# ram.net
KiCad netlist of a schematic drawn in EAGLE
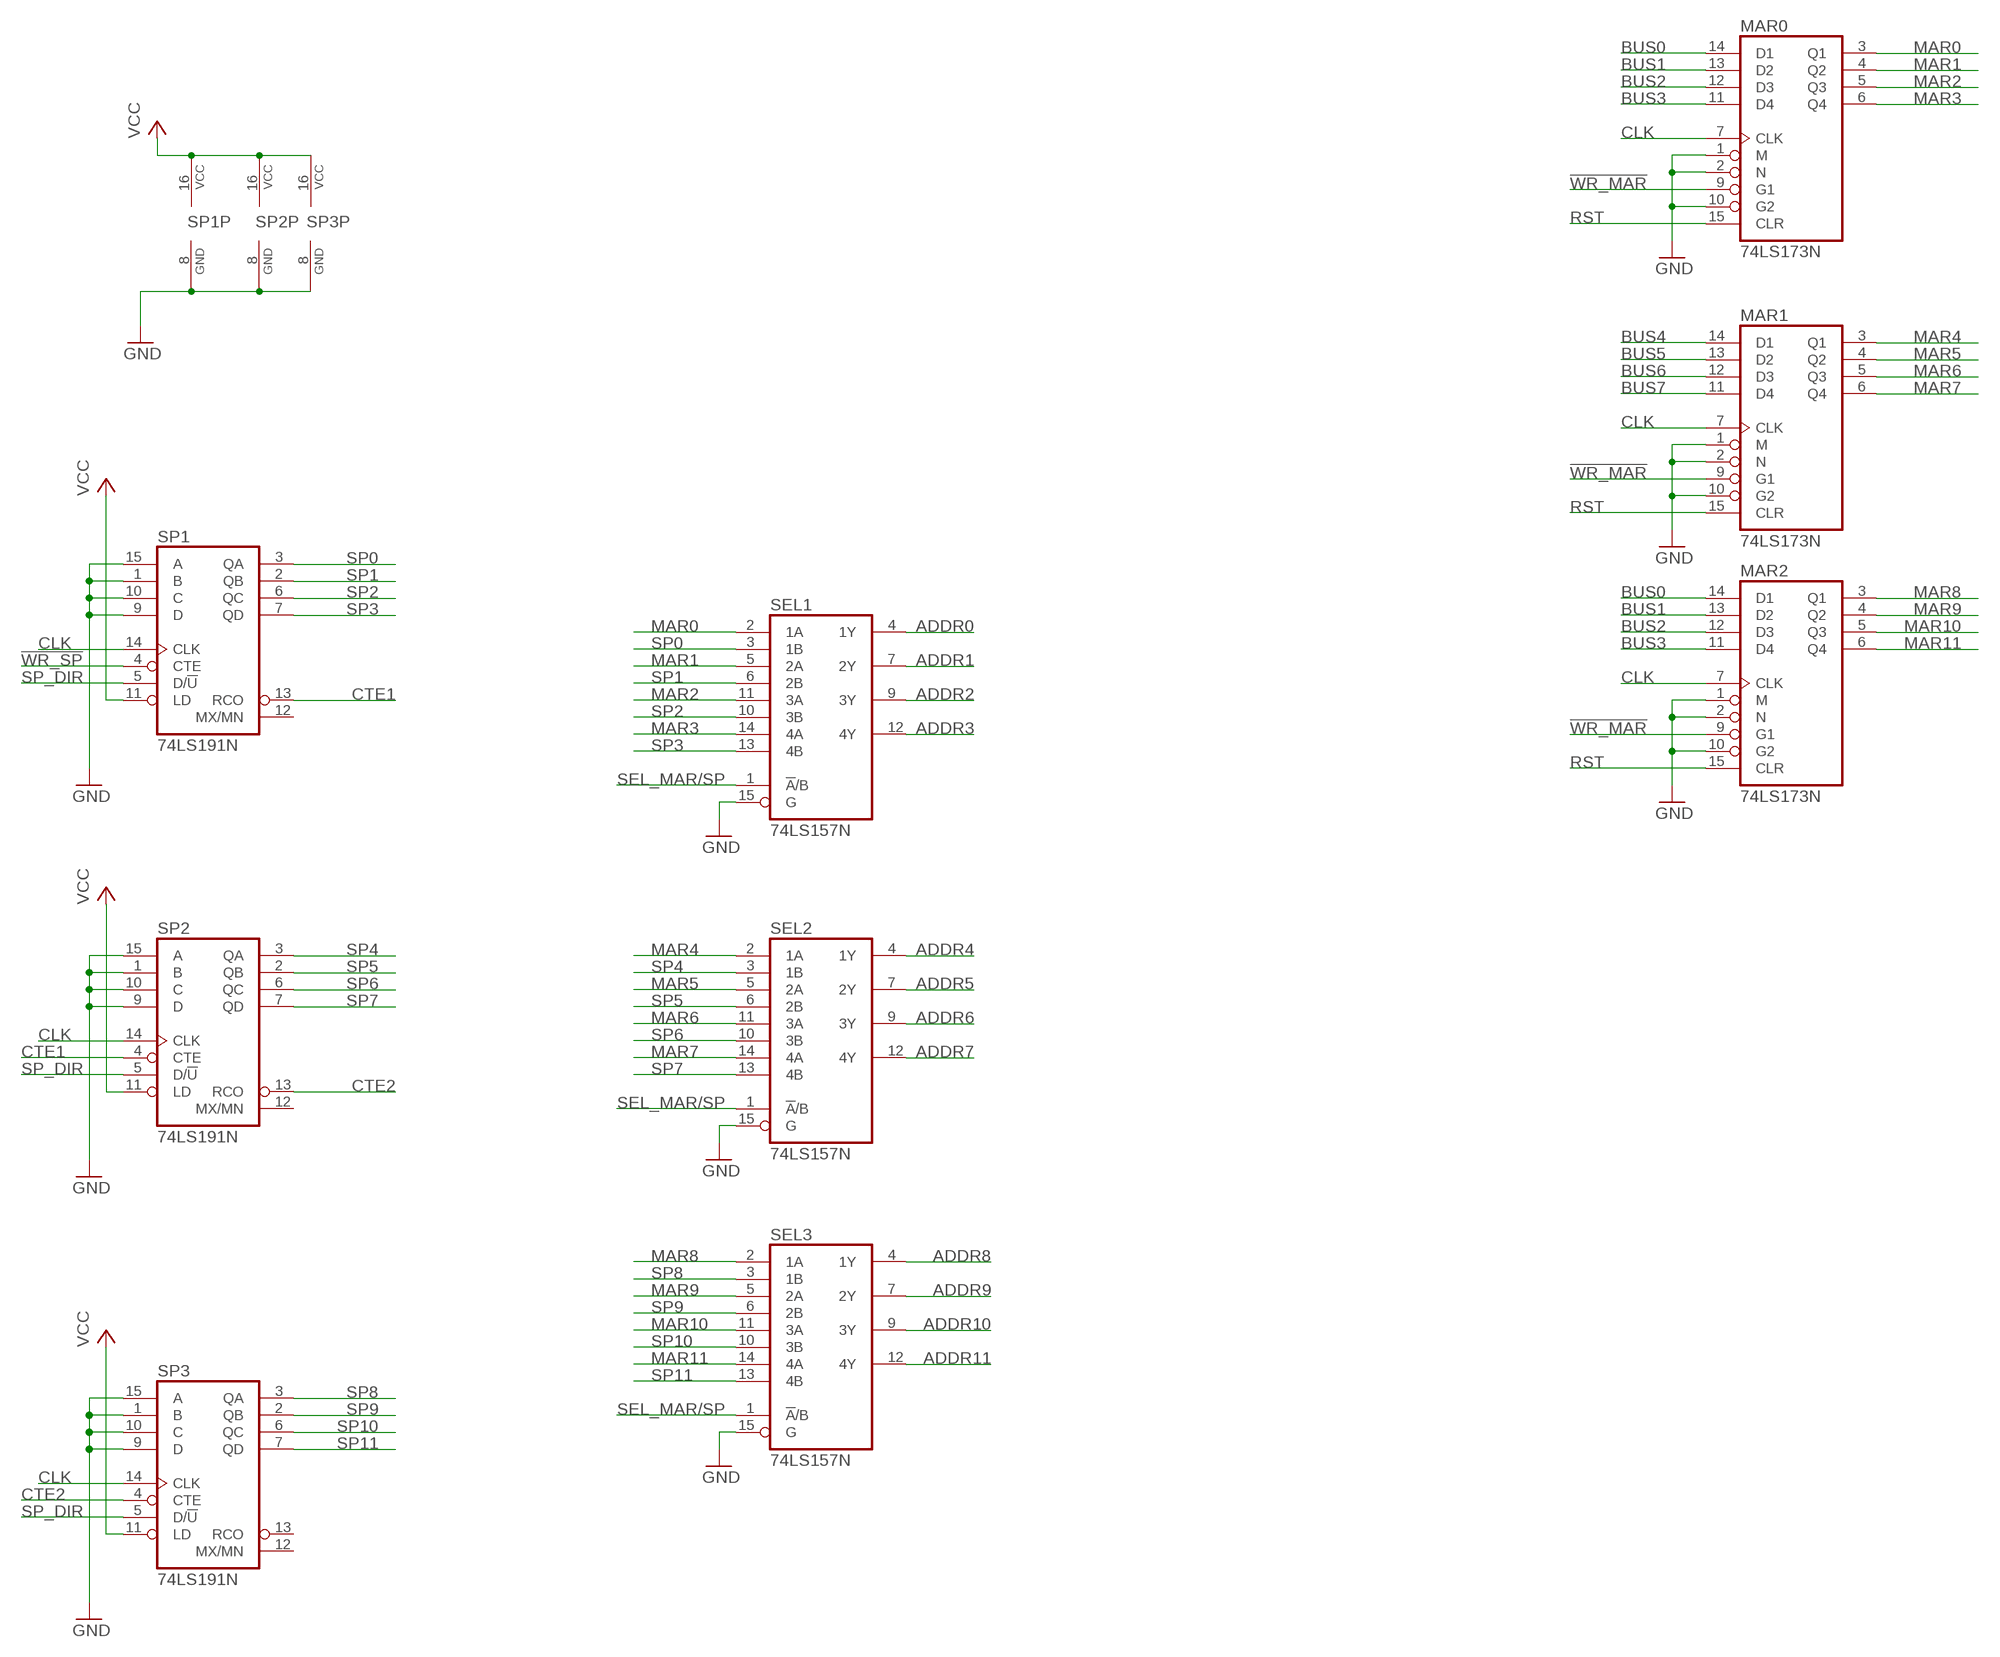
[diagram p0: schematic, sheet 1, part 1 of 2]
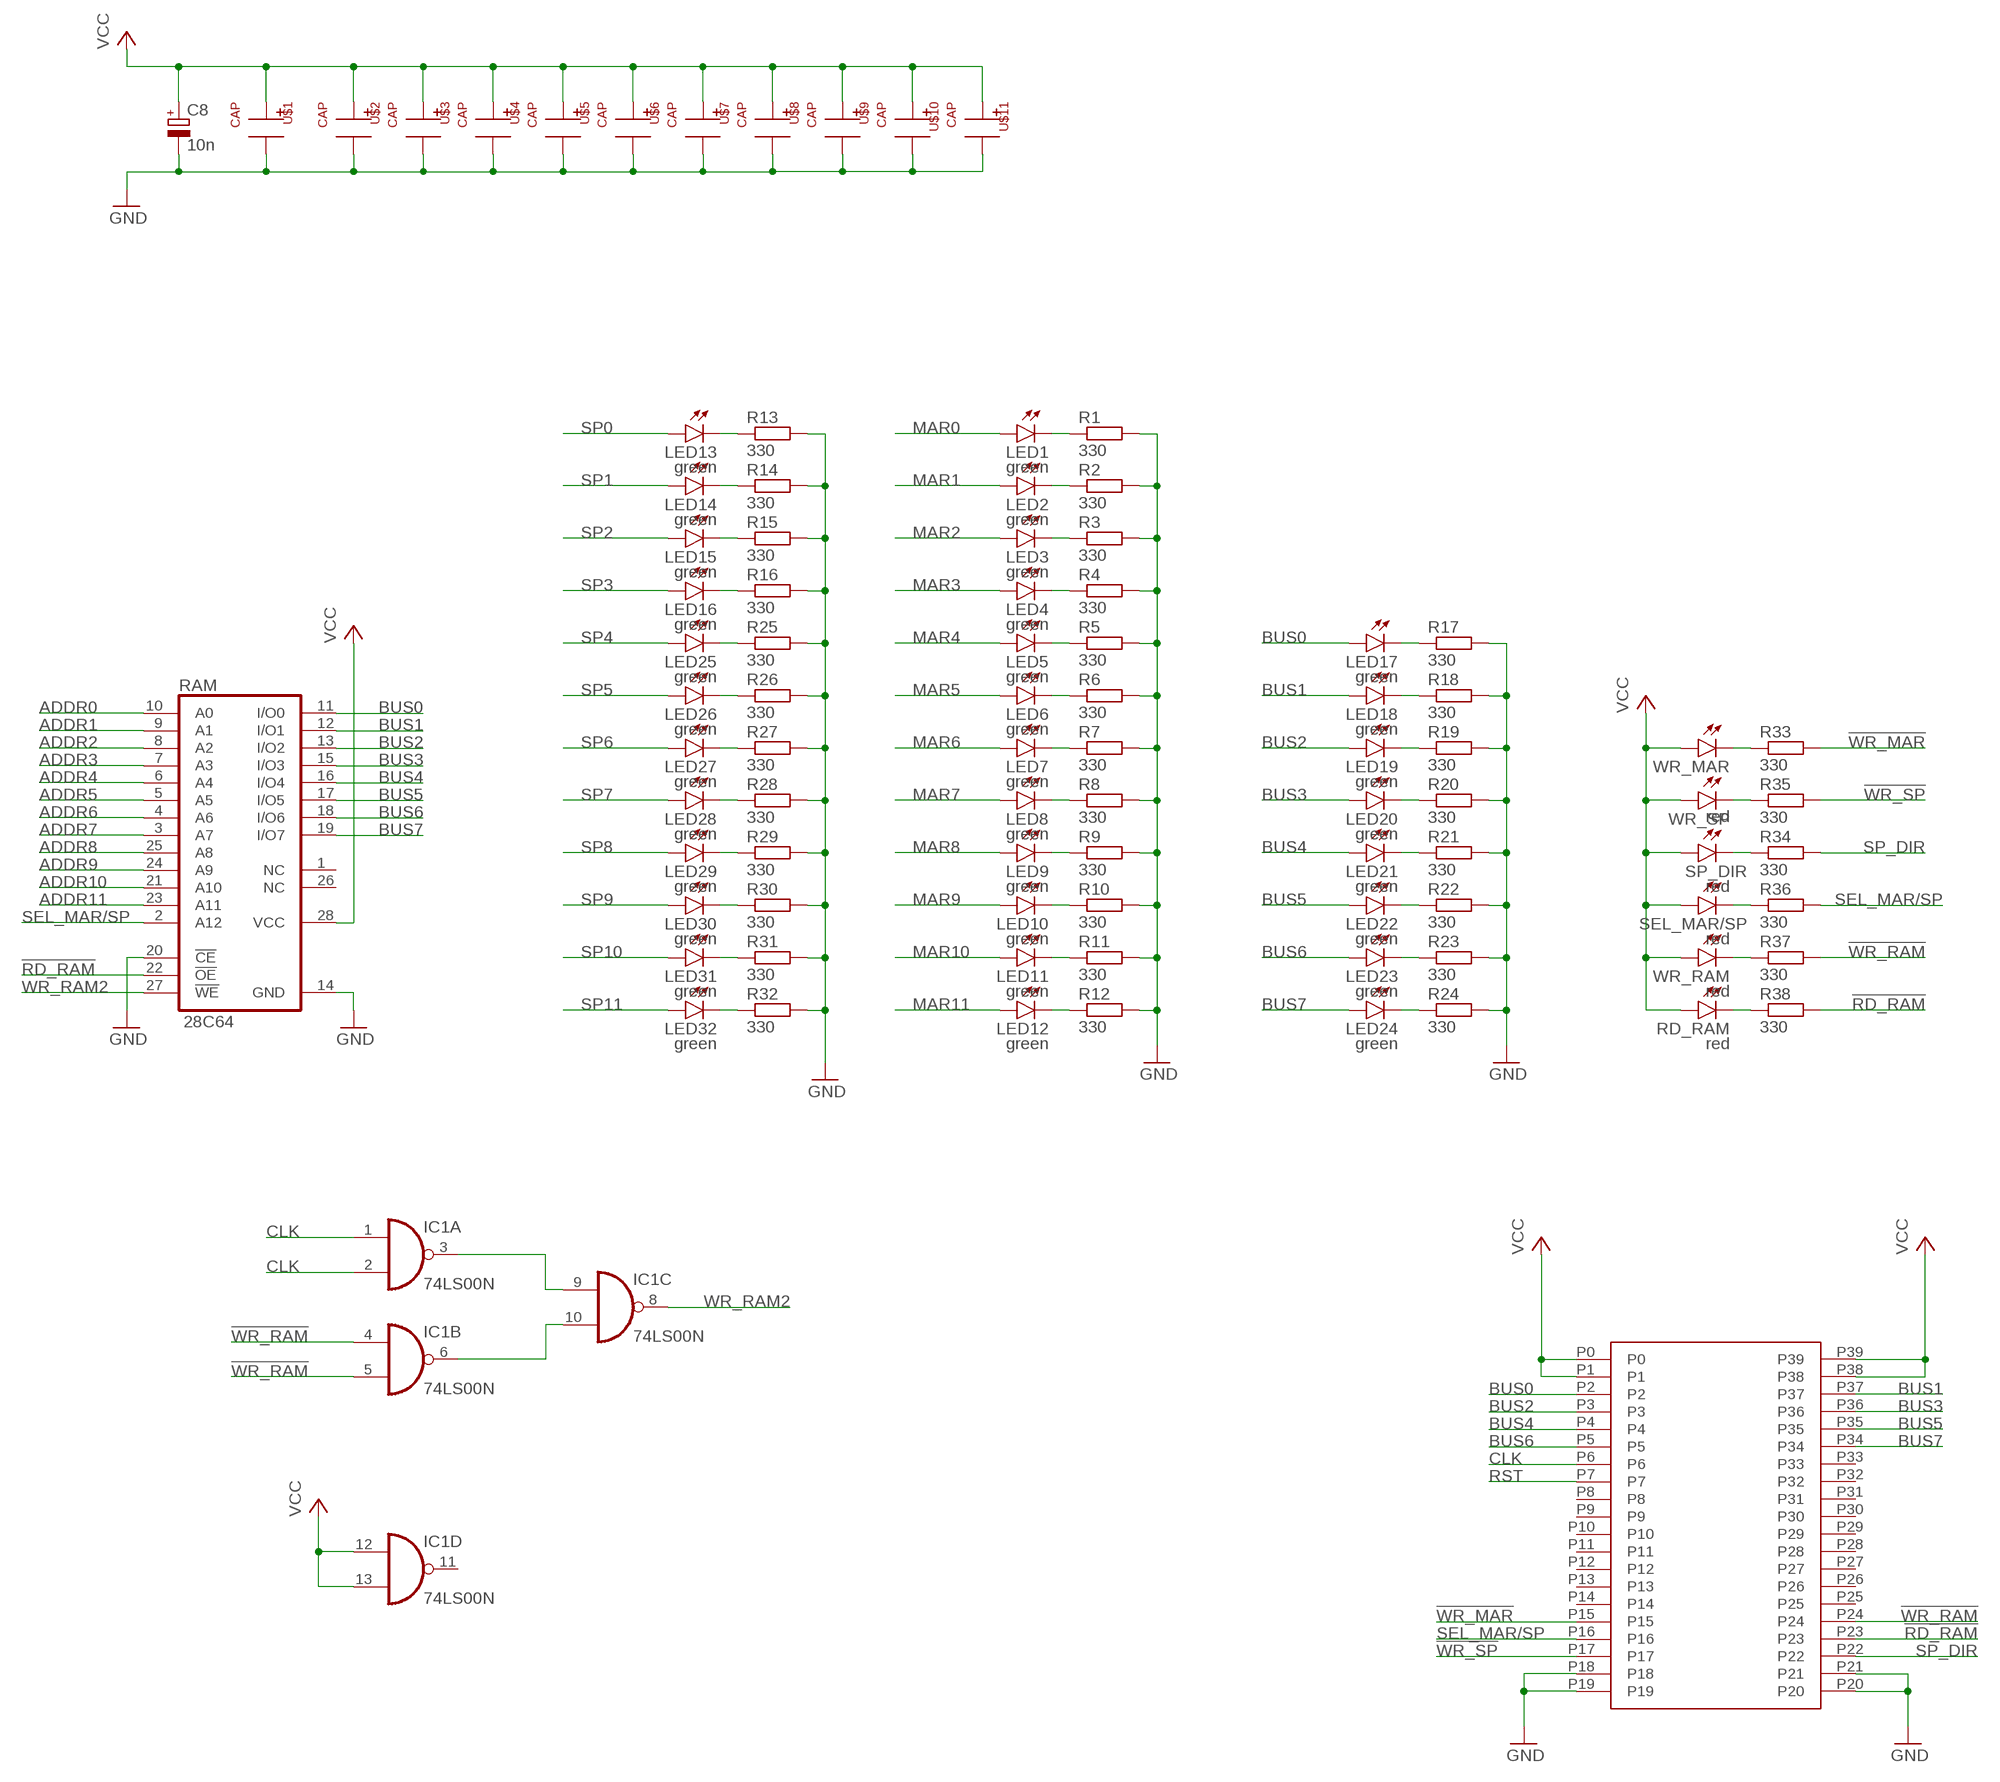
[diagram p1: schematic, sheet 1, part 2 of 2]

(export (version "E")
  (design (tool "Eeschema 10.0.6"))
  (components
    (comp (ref "C8")
      (value "10n")
      (footprint "eagle-import:E2,5-6E")
      (libsource (lib "eagle-import") (part "CPOL-EUE2,5-6E"))
    )
    (comp (ref "IC1")
      (value "74LS00N")
      (footprint "eagle-import:DIL14")
      (libsource (lib "eagle-import") (part "7400NLS"))
    )
    (comp (ref "LED1")
      (value "green")
      (footprint "eagle-import:SML1206")
      (libsource (lib "eagle-import") (part "LEDSML1206"))
    )
    (comp (ref "LED2")
      (value "green")
      (footprint "eagle-import:SML1206")
      (libsource (lib "eagle-import") (part "LEDSML1206"))
    )
    (comp (ref "LED3")
      (value "green")
      (footprint "eagle-import:SML1206")
      (libsource (lib "eagle-import") (part "LEDSML1206"))
    )
    (comp (ref "LED4")
      (value "green")
      (footprint "eagle-import:SML1206")
      (libsource (lib "eagle-import") (part "LEDSML1206"))
    )
    (comp (ref "LED5")
      (value "green")
      (footprint "eagle-import:SML1206")
      (libsource (lib "eagle-import") (part "LEDSML1206"))
    )
    (comp (ref "LED6")
      (value "green")
      (footprint "eagle-import:SML1206")
      (libsource (lib "eagle-import") (part "LEDSML1206"))
    )
    (comp (ref "LED7")
      (value "green")
      (footprint "eagle-import:SML1206")
      (libsource (lib "eagle-import") (part "LEDSML1206"))
    )
    (comp (ref "LED8")
      (value "green")
      (footprint "eagle-import:SML1206")
      (libsource (lib "eagle-import") (part "LEDSML1206"))
    )
    (comp (ref "LED9")
      (value "green")
      (footprint "eagle-import:SML1206")
      (libsource (lib "eagle-import") (part "LEDSML1206"))
    )
    (comp (ref "LED10")
      (value "green")
      (footprint "eagle-import:SML1206")
      (libsource (lib "eagle-import") (part "LEDSML1206"))
    )
    (comp (ref "LED11")
      (value "green")
      (footprint "eagle-import:SML1206")
      (libsource (lib "eagle-import") (part "LEDSML1206"))
    )
    (comp (ref "LED12")
      (value "green")
      (footprint "eagle-import:SML1206")
      (libsource (lib "eagle-import") (part "LEDSML1206"))
    )
    (comp (ref "LED13")
      (value "green")
      (footprint "eagle-import:SML1206")
      (libsource (lib "eagle-import") (part "LEDSML1206"))
    )
    (comp (ref "LED14")
      (value "green")
      (footprint "eagle-import:SML1206")
      (libsource (lib "eagle-import") (part "LEDSML1206"))
    )
    (comp (ref "LED15")
      (value "green")
      (footprint "eagle-import:SML1206")
      (libsource (lib "eagle-import") (part "LEDSML1206"))
    )
    (comp (ref "LED16")
      (value "green")
      (footprint "eagle-import:SML1206")
      (libsource (lib "eagle-import") (part "LEDSML1206"))
    )
    (comp (ref "LED17")
      (value "green")
      (footprint "eagle-import:SML1206")
      (libsource (lib "eagle-import") (part "LEDSML1206"))
    )
    (comp (ref "LED18")
      (value "green")
      (footprint "eagle-import:SML1206")
      (libsource (lib "eagle-import") (part "LEDSML1206"))
    )
    (comp (ref "LED19")
      (value "green")
      (footprint "eagle-import:SML1206")
      (libsource (lib "eagle-import") (part "LEDSML1206"))
    )
    (comp (ref "LED20")
      (value "green")
      (footprint "eagle-import:SML1206")
      (libsource (lib "eagle-import") (part "LEDSML1206"))
    )
    (comp (ref "LED21")
      (value "green")
      (footprint "eagle-import:SML1206")
      (libsource (lib "eagle-import") (part "LEDSML1206"))
    )
    (comp (ref "LED22")
      (value "green")
      (footprint "eagle-import:SML1206")
      (libsource (lib "eagle-import") (part "LEDSML1206"))
    )
    (comp (ref "LED23")
      (value "green")
      (footprint "eagle-import:SML1206")
      (libsource (lib "eagle-import") (part "LEDSML1206"))
    )
    (comp (ref "LED24")
      (value "green")
      (footprint "eagle-import:SML1206")
      (libsource (lib "eagle-import") (part "LEDSML1206"))
    )
    (comp (ref "LED25")
      (value "green")
      (footprint "eagle-import:SML1206")
      (libsource (lib "eagle-import") (part "LEDSML1206"))
    )
    (comp (ref "LED26")
      (value "green")
      (footprint "eagle-import:SML1206")
      (libsource (lib "eagle-import") (part "LEDSML1206"))
    )
    (comp (ref "LED27")
      (value "green")
      (footprint "eagle-import:SML1206")
      (libsource (lib "eagle-import") (part "LEDSML1206"))
    )
    (comp (ref "LED28")
      (value "green")
      (footprint "eagle-import:SML1206")
      (libsource (lib "eagle-import") (part "LEDSML1206"))
    )
    (comp (ref "LED29")
      (value "green")
      (footprint "eagle-import:SML1206")
      (libsource (lib "eagle-import") (part "LEDSML1206"))
    )
    (comp (ref "LED30")
      (value "green")
      (footprint "eagle-import:SML1206")
      (libsource (lib "eagle-import") (part "LEDSML1206"))
    )
    (comp (ref "LED31")
      (value "green")
      (footprint "eagle-import:SML1206")
      (libsource (lib "eagle-import") (part "LEDSML1206"))
    )
    (comp (ref "LED32")
      (value "green")
      (footprint "eagle-import:SML1206")
      (libsource (lib "eagle-import") (part "LEDSML1206"))
    )
    (comp (ref "MAR0")
      (value "74LS173N")
      (footprint "eagle-import:DIL16")
      (libsource (lib "eagle-import") (part "74173NLS"))
    )
    (comp (ref "MAR1")
      (value "74LS173N")
      (footprint "eagle-import:DIL16")
      (libsource (lib "eagle-import") (part "74173NLS"))
    )
    (comp (ref "MAR2")
      (value "74LS173N")
      (footprint "eagle-import:DIL16")
      (libsource (lib "eagle-import") (part "74173NLS"))
    )
    (comp (ref "R1")
      (value "330")
      (footprint "eagle-import:R0805")
      (libsource (lib "eagle-import") (part "R-EU_R0805"))
    )
    (comp (ref "R2")
      (value "330")
      (footprint "eagle-import:R0805")
      (libsource (lib "eagle-import") (part "R-EU_R0805"))
    )
    (comp (ref "R3")
      (value "330")
      (footprint "eagle-import:R0805")
      (libsource (lib "eagle-import") (part "R-EU_R0805"))
    )
    (comp (ref "R4")
      (value "330")
      (footprint "eagle-import:R0805")
      (libsource (lib "eagle-import") (part "R-EU_R0805"))
    )
    (comp (ref "R5")
      (value "330")
      (footprint "eagle-import:R0805")
      (libsource (lib "eagle-import") (part "R-EU_R0805"))
    )
    (comp (ref "R6")
      (value "330")
      (footprint "eagle-import:R0805")
      (libsource (lib "eagle-import") (part "R-EU_R0805"))
    )
    (comp (ref "R7")
      (value "330")
      (footprint "eagle-import:R0805")
      (libsource (lib "eagle-import") (part "R-EU_R0805"))
    )
    (comp (ref "R8")
      (value "330")
      (footprint "eagle-import:R0805")
      (libsource (lib "eagle-import") (part "R-EU_R0805"))
    )
    (comp (ref "R9")
      (value "330")
      (footprint "eagle-import:R0805")
      (libsource (lib "eagle-import") (part "R-EU_R0805"))
    )
    (comp (ref "R10")
      (value "330")
      (footprint "eagle-import:R0805")
      (libsource (lib "eagle-import") (part "R-EU_R0805"))
    )
    (comp (ref "R11")
      (value "330")
      (footprint "eagle-import:R0805")
      (libsource (lib "eagle-import") (part "R-EU_R0805"))
    )
    (comp (ref "R12")
      (value "330")
      (footprint "eagle-import:R0805")
      (libsource (lib "eagle-import") (part "R-EU_R0805"))
    )
    (comp (ref "R13")
      (value "330")
      (footprint "eagle-import:R0805")
      (libsource (lib "eagle-import") (part "R-EU_R0805"))
    )
    (comp (ref "R14")
      (value "330")
      (footprint "eagle-import:R0805")
      (libsource (lib "eagle-import") (part "R-EU_R0805"))
    )
    (comp (ref "R15")
      (value "330")
      (footprint "eagle-import:R0805")
      (libsource (lib "eagle-import") (part "R-EU_R0805"))
    )
    (comp (ref "R16")
      (value "330")
      (footprint "eagle-import:R0805")
      (libsource (lib "eagle-import") (part "R-EU_R0805"))
    )
    (comp (ref "R17")
      (value "330")
      (footprint "eagle-import:R0805")
      (libsource (lib "eagle-import") (part "R-EU_R0805"))
    )
    (comp (ref "R18")
      (value "330")
      (footprint "eagle-import:R0805")
      (libsource (lib "eagle-import") (part "R-EU_R0805"))
    )
    (comp (ref "R19")
      (value "330")
      (footprint "eagle-import:R0805")
      (libsource (lib "eagle-import") (part "R-EU_R0805"))
    )
    (comp (ref "R20")
      (value "330")
      (footprint "eagle-import:R0805")
      (libsource (lib "eagle-import") (part "R-EU_R0805"))
    )
    (comp (ref "R21")
      (value "330")
      (footprint "eagle-import:R0805")
      (libsource (lib "eagle-import") (part "R-EU_R0805"))
    )
    (comp (ref "R22")
      (value "330")
      (footprint "eagle-import:R0805")
      (libsource (lib "eagle-import") (part "R-EU_R0805"))
    )
    (comp (ref "R23")
      (value "330")
      (footprint "eagle-import:R0805")
      (libsource (lib "eagle-import") (part "R-EU_R0805"))
    )
    (comp (ref "R24")
      (value "330")
      (footprint "eagle-import:R0805")
      (libsource (lib "eagle-import") (part "R-EU_R0805"))
    )
    (comp (ref "R25")
      (value "330")
      (footprint "eagle-import:R0805")
      (libsource (lib "eagle-import") (part "R-EU_R0805"))
    )
    (comp (ref "R26")
      (value "330")
      (footprint "eagle-import:R0805")
      (libsource (lib "eagle-import") (part "R-EU_R0805"))
    )
    (comp (ref "R27")
      (value "330")
      (footprint "eagle-import:R0805")
      (libsource (lib "eagle-import") (part "R-EU_R0805"))
    )
    (comp (ref "R28")
      (value "330")
      (footprint "eagle-import:R0805")
      (libsource (lib "eagle-import") (part "R-EU_R0805"))
    )
    (comp (ref "R29")
      (value "330")
      (footprint "eagle-import:R0805")
      (libsource (lib "eagle-import") (part "R-EU_R0805"))
    )
    (comp (ref "R30")
      (value "330")
      (footprint "eagle-import:R0805")
      (libsource (lib "eagle-import") (part "R-EU_R0805"))
    )
    (comp (ref "R31")
      (value "330")
      (footprint "eagle-import:R0805")
      (libsource (lib "eagle-import") (part "R-EU_R0805"))
    )
    (comp (ref "R32")
      (value "330")
      (footprint "eagle-import:R0805")
      (libsource (lib "eagle-import") (part "R-EU_R0805"))
    )
    (comp (ref "R33")
      (value "330")
      (footprint "eagle-import:R0805")
      (libsource (lib "eagle-import") (part "R-EU_R0805"))
    )
    (comp (ref "R34")
      (value "330")
      (footprint "eagle-import:R0805")
      (libsource (lib "eagle-import") (part "R-EU_R0805"))
    )
    (comp (ref "R35")
      (value "330")
      (footprint "eagle-import:R0805")
      (libsource (lib "eagle-import") (part "R-EU_R0805"))
    )
    (comp (ref "R36")
      (value "330")
      (footprint "eagle-import:R0805")
      (libsource (lib "eagle-import") (part "R-EU_R0805"))
    )
    (comp (ref "R37")
      (value "330")
      (footprint "eagle-import:R0805")
      (libsource (lib "eagle-import") (part "R-EU_R0805"))
    )
    (comp (ref "R38")
      (value "330")
      (footprint "eagle-import:R0805")
      (libsource (lib "eagle-import") (part "R-EU_R0805"))
    )
    (comp (ref "RAM")
      (value "28C64")
      (footprint "eagle-import:DIL28-6")
      (fields (field (name "MPN") "AT28C64B-15PU"))
      (libsource (lib "eagle-import") (part "28C64C"))
    )
    (comp (ref "RD_RAM")
      (value "red")
      (footprint "eagle-import:SML1206")
      (libsource (lib "eagle-import") (part "LEDSML1206"))
    )
    (comp (ref "SEL1")
      (value "74LS157N")
      (footprint "eagle-import:DIL16")
      (libsource (lib "eagle-import") (part "74157NLS"))
    )
    (comp (ref "SEL2")
      (value "74LS157N")
      (footprint "eagle-import:DIL16")
      (libsource (lib "eagle-import") (part "74157NLS"))
    )
    (comp (ref "SEL3")
      (value "74LS157N")
      (footprint "eagle-import:DIL16")
      (libsource (lib "eagle-import") (part "74157NLS"))
    )
    (comp (ref "SEL_MAR/SP")
      (value "red")
      (footprint "eagle-import:SML1206")
      (libsource (lib "eagle-import") (part "LEDSML1206"))
    )
    (comp (ref "SP1")
      (value "74LS191N")
      (footprint "eagle-import:DIL16")
      (libsource (lib "eagle-import") (part "74191NLS"))
    )
    (comp (ref "SP2")
      (value "74LS191N")
      (footprint "eagle-import:DIL16")
      (libsource (lib "eagle-import") (part "74191NLS"))
    )
    (comp (ref "SP3")
      (value "74LS191N")
      (footprint "eagle-import:DIL16")
      (libsource (lib "eagle-import") (part "74191NLS"))
    )
    (comp (ref "SP_DIR")
      (value "red")
      (footprint "eagle-import:SML1206")
      (libsource (lib "eagle-import") (part "LEDSML1206"))
    )
    (comp (ref "U$1")
      (value "CAP")
      (footprint "eagle-import:CAP")
      (libsource (lib "eagle-import") (part "CAP"))
    )
    (comp (ref "U$2")
      (value "CAP")
      (footprint "eagle-import:CAP")
      (libsource (lib "eagle-import") (part "CAP"))
    )
    (comp (ref "U$3")
      (value "CAP")
      (footprint "eagle-import:CAP")
      (libsource (lib "eagle-import") (part "CAP"))
    )
    (comp (ref "U$4")
      (value "CAP")
      (footprint "eagle-import:CAP")
      (libsource (lib "eagle-import") (part "CAP"))
    )
    (comp (ref "U$5")
      (value "CAP")
      (footprint "eagle-import:CAP")
      (libsource (lib "eagle-import") (part "CAP"))
    )
    (comp (ref "U$6")
      (value "CAP")
      (footprint "eagle-import:CAP")
      (libsource (lib "eagle-import") (part "CAP"))
    )
    (comp (ref "U$7")
      (value "CAP")
      (footprint "eagle-import:CAP")
      (libsource (lib "eagle-import") (part "CAP"))
    )
    (comp (ref "U$8")
      (value "CAP")
      (footprint "eagle-import:CAP")
      (libsource (lib "eagle-import") (part "CAP"))
    )
    (comp (ref "U$9")
      (value "CAP")
      (footprint "eagle-import:CAP")
      (libsource (lib "eagle-import") (part "CAP"))
    )
    (comp (ref "U$10")
      (value "CAP")
      (footprint "eagle-import:CAP")
      (libsource (lib "eagle-import") (part "CAP"))
    )
    (comp (ref "U$11")
      (value "CAP")
      (footprint "eagle-import:CAP")
      (libsource (lib "eagle-import") (part "CAP"))
    )
    (comp (ref "U$12")
      (value "2X40")
      (footprint "eagle-import:2X40")
      (libsource (lib "eagle-import") (part "2X40"))
    )
    (comp (ref "WR_MAR")
      (value "red")
      (footprint "eagle-import:SML1206")
      (libsource (lib "eagle-import") (part "LEDSML1206"))
    )
    (comp (ref "WR_RAM")
      (value "red")
      (footprint "eagle-import:SML1206")
      (libsource (lib "eagle-import") (part "LEDSML1206"))
    )
    (comp (ref "WR_SP")
      (value "red")
      (footprint "eagle-import:SML1206")
      (libsource (lib "eagle-import") (part "LEDSML1206"))
    )
  )
  (nets
    (net (code "1") (name "/ADDR0") (class "Default")
      (node (ref "RAM") (pin "10") (pinfunction "A0_10") (pintype "input"))
      (node (ref "SEL1") (pin "4") (pinfunction "1Y_4") (pintype "output"))
    )
    (net (code "2") (name "/ADDR1") (class "Default")
      (node (ref "RAM") (pin "9") (pinfunction "A1_9") (pintype "input"))
      (node (ref "SEL1") (pin "7") (pinfunction "2Y_7") (pintype "output"))
    )
    (net (code "3") (name "/ADDR2") (class "Default")
      (node (ref "RAM") (pin "8") (pinfunction "A2_8") (pintype "input"))
      (node (ref "SEL1") (pin "9") (pinfunction "3Y_9") (pintype "output"))
    )
    (net (code "4") (name "/ADDR3") (class "Default")
      (node (ref "RAM") (pin "7") (pinfunction "A3_7") (pintype "input"))
      (node (ref "SEL1") (pin "12") (pinfunction "4Y_12") (pintype "output"))
    )
    (net (code "5") (name "/ADDR4") (class "Default")
      (node (ref "RAM") (pin "6") (pinfunction "A4_6") (pintype "input"))
      (node (ref "SEL2") (pin "4") (pinfunction "1Y_4") (pintype "output"))
    )
    (net (code "6") (name "/ADDR5") (class "Default")
      (node (ref "RAM") (pin "5") (pinfunction "A5_5") (pintype "input"))
      (node (ref "SEL2") (pin "7") (pinfunction "2Y_7") (pintype "output"))
    )
    (net (code "7") (name "/ADDR6") (class "Default")
      (node (ref "RAM") (pin "4") (pinfunction "A6_4") (pintype "input"))
      (node (ref "SEL2") (pin "9") (pinfunction "3Y_9") (pintype "output"))
    )
    (net (code "8") (name "/ADDR7") (class "Default")
      (node (ref "RAM") (pin "3") (pinfunction "A7_3") (pintype "input"))
      (node (ref "SEL2") (pin "12") (pinfunction "4Y_12") (pintype "output"))
    )
    (net (code "9") (name "/ADDR8") (class "Default")
      (node (ref "RAM") (pin "25") (pinfunction "A8_25") (pintype "input"))
      (node (ref "SEL3") (pin "4") (pinfunction "1Y_4") (pintype "output"))
    )
    (net (code "10") (name "/ADDR9") (class "Default")
      (node (ref "RAM") (pin "24") (pinfunction "A9_24") (pintype "input"))
      (node (ref "SEL3") (pin "7") (pinfunction "2Y_7") (pintype "output"))
    )
    (net (code "11") (name "/ADDR10") (class "Default")
      (node (ref "RAM") (pin "21") (pinfunction "A10_21") (pintype "input"))
      (node (ref "SEL3") (pin "9") (pinfunction "3Y_9") (pintype "output"))
    )
    (net (code "12") (name "/ADDR11") (class "Default")
      (node (ref "RAM") (pin "23") (pinfunction "A11_23") (pintype "input"))
      (node (ref "SEL3") (pin "12") (pinfunction "4Y_12") (pintype "output"))
    )
    (net (code "13") (name "/BUS0") (class "Default")
      (node (ref "LED17") (pin "A") (pinfunction "A_A") (pintype "passive"))
      (node (ref "MAR0") (pin "14") (pinfunction "D1_14") (pintype "input"))
      (node (ref "MAR2") (pin "14") (pinfunction "D1_14") (pintype "input"))
      (node (ref "RAM") (pin "11") (pinfunction "I/O0_11") (pintype "bidirectional"))
      (node (ref "U$12") (pin "P2") (pinfunction "P2_P2") (pintype "bidirectional"))
    )
    (net (code "14") (name "/BUS1") (class "Default")
      (node (ref "LED18") (pin "A") (pinfunction "A_A") (pintype "passive"))
      (node (ref "MAR0") (pin "13") (pinfunction "D2_13") (pintype "input"))
      (node (ref "MAR2") (pin "13") (pinfunction "D2_13") (pintype "input"))
      (node (ref "RAM") (pin "12") (pinfunction "I/O1_12") (pintype "bidirectional"))
      (node (ref "U$12") (pin "P37") (pinfunction "P37_P37") (pintype "bidirectional"))
    )
    (net (code "15") (name "/BUS2") (class "Default")
      (node (ref "LED19") (pin "A") (pinfunction "A_A") (pintype "passive"))
      (node (ref "MAR0") (pin "12") (pinfunction "D3_12") (pintype "input"))
      (node (ref "MAR2") (pin "12") (pinfunction "D3_12") (pintype "input"))
      (node (ref "RAM") (pin "13") (pinfunction "I/O2_13") (pintype "bidirectional"))
      (node (ref "U$12") (pin "P3") (pinfunction "P3_P3") (pintype "bidirectional"))
    )
    (net (code "16") (name "/BUS3") (class "Default")
      (node (ref "LED20") (pin "A") (pinfunction "A_A") (pintype "passive"))
      (node (ref "MAR0") (pin "11") (pinfunction "D4_11") (pintype "input"))
      (node (ref "MAR2") (pin "11") (pinfunction "D4_11") (pintype "input"))
      (node (ref "RAM") (pin "15") (pinfunction "I/O3_15") (pintype "bidirectional"))
      (node (ref "U$12") (pin "P36") (pinfunction "P36_P36") (pintype "bidirectional"))
    )
    (net (code "17") (name "/BUS4") (class "Default")
      (node (ref "LED21") (pin "A") (pinfunction "A_A") (pintype "passive"))
      (node (ref "MAR1") (pin "14") (pinfunction "D1_14") (pintype "input"))
      (node (ref "RAM") (pin "16") (pinfunction "I/O4_16") (pintype "bidirectional"))
      (node (ref "U$12") (pin "P4") (pinfunction "P4_P4") (pintype "bidirectional"))
    )
    (net (code "18") (name "/BUS5") (class "Default")
      (node (ref "LED22") (pin "A") (pinfunction "A_A") (pintype "passive"))
      (node (ref "MAR1") (pin "13") (pinfunction "D2_13") (pintype "input"))
      (node (ref "RAM") (pin "17") (pinfunction "I/O5_17") (pintype "bidirectional"))
      (node (ref "U$12") (pin "P35") (pinfunction "P35_P35") (pintype "bidirectional"))
    )
    (net (code "19") (name "/BUS6") (class "Default")
      (node (ref "LED23") (pin "A") (pinfunction "A_A") (pintype "passive"))
      (node (ref "MAR1") (pin "12") (pinfunction "D3_12") (pintype "input"))
      (node (ref "RAM") (pin "18") (pinfunction "I/O6_18") (pintype "bidirectional"))
      (node (ref "U$12") (pin "P5") (pinfunction "P5_P5") (pintype "bidirectional"))
    )
    (net (code "20") (name "/BUS7") (class "Default")
      (node (ref "LED24") (pin "A") (pinfunction "A_A") (pintype "passive"))
      (node (ref "MAR1") (pin "11") (pinfunction "D4_11") (pintype "input"))
      (node (ref "RAM") (pin "19") (pinfunction "I/O7_19") (pintype "bidirectional"))
      (node (ref "U$12") (pin "P34") (pinfunction "P34_P34") (pintype "bidirectional"))
    )
    (net (code "21") (name "/CLK") (class "Default")
      (node (ref "IC1") (pin "1") (pinfunction "I0_1") (pintype "input"))
      (node (ref "IC1") (pin "2") (pinfunction "I1_2") (pintype "input"))
      (node (ref "MAR0") (pin "7") (pinfunction "CLK_7") (pintype "input"))
      (node (ref "MAR1") (pin "7") (pinfunction "CLK_7") (pintype "input"))
      (node (ref "MAR2") (pin "7") (pinfunction "CLK_7") (pintype "input"))
      (node (ref "SP1") (pin "14") (pinfunction "CLK_14") (pintype "input"))
      (node (ref "SP2") (pin "14") (pinfunction "CLK_14") (pintype "input"))
      (node (ref "SP3") (pin "14") (pinfunction "CLK_14") (pintype "input"))
      (node (ref "U$12") (pin "P6") (pinfunction "P6_P6") (pintype "bidirectional"))
    )
    (net (code "22") (name "/CTE1") (class "Default")
      (node (ref "SP1") (pin "13") (pinfunction "RCO_13") (pintype "output"))
      (node (ref "SP2") (pin "4") (pinfunction "CTE_4") (pintype "input"))
    )
    (net (code "23") (name "/CTE2") (class "Default")
      (node (ref "SP2") (pin "13") (pinfunction "RCO_13") (pintype "output"))
      (node (ref "SP3") (pin "4") (pinfunction "CTE_4") (pintype "input"))
    )
    (net (code "24") (name "/MAR0") (class "Default")
      (node (ref "LED1") (pin "A") (pinfunction "A_A") (pintype "passive"))
      (node (ref "MAR0") (pin "3") (pinfunction "Q1_3") (pintype "tri_state"))
      (node (ref "SEL1") (pin "2") (pinfunction "1A_2") (pintype "input"))
    )
    (net (code "25") (name "/MAR1") (class "Default")
      (node (ref "LED2") (pin "A") (pinfunction "A_A") (pintype "passive"))
      (node (ref "MAR0") (pin "4") (pinfunction "Q2_4") (pintype "tri_state"))
      (node (ref "SEL1") (pin "5") (pinfunction "2A_5") (pintype "input"))
    )
    (net (code "26") (name "/MAR2") (class "Default")
      (node (ref "LED3") (pin "A") (pinfunction "A_A") (pintype "passive"))
      (node (ref "MAR0") (pin "5") (pinfunction "Q3_5") (pintype "tri_state"))
      (node (ref "SEL1") (pin "11") (pinfunction "3A_11") (pintype "input"))
    )
    (net (code "27") (name "/MAR3") (class "Default")
      (node (ref "LED4") (pin "A") (pinfunction "A_A") (pintype "passive"))
      (node (ref "MAR0") (pin "6") (pinfunction "Q4_6") (pintype "tri_state"))
      (node (ref "SEL1") (pin "14") (pinfunction "4A_14") (pintype "input"))
    )
    (net (code "28") (name "/MAR4") (class "Default")
      (node (ref "LED5") (pin "A") (pinfunction "A_A") (pintype "passive"))
      (node (ref "MAR1") (pin "3") (pinfunction "Q1_3") (pintype "tri_state"))
      (node (ref "SEL2") (pin "2") (pinfunction "1A_2") (pintype "input"))
    )
    (net (code "29") (name "/MAR5") (class "Default")
      (node (ref "LED6") (pin "A") (pinfunction "A_A") (pintype "passive"))
      (node (ref "MAR1") (pin "4") (pinfunction "Q2_4") (pintype "tri_state"))
      (node (ref "SEL2") (pin "5") (pinfunction "2A_5") (pintype "input"))
    )
    (net (code "30") (name "/MAR6") (class "Default")
      (node (ref "LED7") (pin "A") (pinfunction "A_A") (pintype "passive"))
      (node (ref "MAR1") (pin "5") (pinfunction "Q3_5") (pintype "tri_state"))
      (node (ref "SEL2") (pin "11") (pinfunction "3A_11") (pintype "input"))
    )
    (net (code "31") (name "/MAR7") (class "Default")
      (node (ref "LED8") (pin "A") (pinfunction "A_A") (pintype "passive"))
      (node (ref "MAR1") (pin "6") (pinfunction "Q4_6") (pintype "tri_state"))
      (node (ref "SEL2") (pin "14") (pinfunction "4A_14") (pintype "input"))
    )
    (net (code "32") (name "/MAR8") (class "Default")
      (node (ref "LED9") (pin "A") (pinfunction "A_A") (pintype "passive"))
      (node (ref "MAR2") (pin "3") (pinfunction "Q1_3") (pintype "tri_state"))
      (node (ref "SEL3") (pin "2") (pinfunction "1A_2") (pintype "input"))
    )
    (net (code "33") (name "/MAR9") (class "Default")
      (node (ref "LED10") (pin "A") (pinfunction "A_A") (pintype "passive"))
      (node (ref "MAR2") (pin "4") (pinfunction "Q2_4") (pintype "tri_state"))
      (node (ref "SEL3") (pin "5") (pinfunction "2A_5") (pintype "input"))
    )
    (net (code "34") (name "/MAR10") (class "Default")
      (node (ref "LED11") (pin "A") (pinfunction "A_A") (pintype "passive"))
      (node (ref "MAR2") (pin "5") (pinfunction "Q3_5") (pintype "tri_state"))
      (node (ref "SEL3") (pin "11") (pinfunction "3A_11") (pintype "input"))
    )
    (net (code "35") (name "/MAR11") (class "Default")
      (node (ref "LED12") (pin "A") (pinfunction "A_A") (pintype "passive"))
      (node (ref "MAR2") (pin "6") (pinfunction "Q4_6") (pintype "tri_state"))
      (node (ref "SEL3") (pin "14") (pinfunction "4A_14") (pintype "input"))
    )
    (net (code "36") (name "/RST") (class "Default")
      (node (ref "MAR0") (pin "15") (pinfunction "CLR_15") (pintype "input"))
      (node (ref "MAR1") (pin "15") (pinfunction "CLR_15") (pintype "input"))
      (node (ref "MAR2") (pin "15") (pinfunction "CLR_15") (pintype "input"))
      (node (ref "U$12") (pin "P7") (pinfunction "P7_P7") (pintype "bidirectional"))
    )
    (net (code "37") (name "/SEL_MAR{slash}SP") (class "Default")
      (node (ref "R36") (pin "2") (pinfunction "2_2") (pintype "passive"))
      (node (ref "RAM") (pin "2") (pinfunction "A12_2") (pintype "input"))
      (node (ref "SEL1") (pin "1") (pinfunction "~{A}/B_1") (pintype "input"))
      (node (ref "SEL2") (pin "1") (pinfunction "~{A}/B_1") (pintype "input"))
      (node (ref "SEL3") (pin "1") (pinfunction "~{A}/B_1") (pintype "input"))
      (node (ref "U$12") (pin "P16") (pinfunction "P16_P16") (pintype "bidirectional"))
    )
    (net (code "38") (name "/SP0") (class "Default")
      (node (ref "LED13") (pin "A") (pinfunction "A_A") (pintype "passive"))
      (node (ref "SEL1") (pin "3") (pinfunction "1B_3") (pintype "input"))
      (node (ref "SP1") (pin "3") (pinfunction "QA_3") (pintype "output"))
    )
    (net (code "39") (name "/SP1") (class "Default")
      (node (ref "LED14") (pin "A") (pinfunction "A_A") (pintype "passive"))
      (node (ref "SEL1") (pin "6") (pinfunction "2B_6") (pintype "input"))
      (node (ref "SP1") (pin "2") (pinfunction "QB_2") (pintype "output"))
    )
    (net (code "40") (name "/SP2") (class "Default")
      (node (ref "LED15") (pin "A") (pinfunction "A_A") (pintype "passive"))
      (node (ref "SEL1") (pin "10") (pinfunction "3B_10") (pintype "input"))
      (node (ref "SP1") (pin "6") (pinfunction "QC_6") (pintype "output"))
    )
    (net (code "41") (name "/SP3") (class "Default")
      (node (ref "LED16") (pin "A") (pinfunction "A_A") (pintype "passive"))
      (node (ref "SEL1") (pin "13") (pinfunction "4B_13") (pintype "input"))
      (node (ref "SP1") (pin "7") (pinfunction "QD_7") (pintype "output"))
    )
    (net (code "42") (name "/SP4") (class "Default")
      (node (ref "LED25") (pin "A") (pinfunction "A_A") (pintype "passive"))
      (node (ref "SEL2") (pin "3") (pinfunction "1B_3") (pintype "input"))
      (node (ref "SP2") (pin "3") (pinfunction "QA_3") (pintype "output"))
    )
    (net (code "43") (name "/SP5") (class "Default")
      (node (ref "LED26") (pin "A") (pinfunction "A_A") (pintype "passive"))
      (node (ref "SEL2") (pin "6") (pinfunction "2B_6") (pintype "input"))
      (node (ref "SP2") (pin "2") (pinfunction "QB_2") (pintype "output"))
    )
    (net (code "44") (name "/SP6") (class "Default")
      (node (ref "LED27") (pin "A") (pinfunction "A_A") (pintype "passive"))
      (node (ref "SEL2") (pin "10") (pinfunction "3B_10") (pintype "input"))
      (node (ref "SP2") (pin "6") (pinfunction "QC_6") (pintype "output"))
    )
    (net (code "45") (name "/SP7") (class "Default")
      (node (ref "LED28") (pin "A") (pinfunction "A_A") (pintype "passive"))
      (node (ref "SEL2") (pin "13") (pinfunction "4B_13") (pintype "input"))
      (node (ref "SP2") (pin "7") (pinfunction "QD_7") (pintype "output"))
    )
    (net (code "46") (name "/SP8") (class "Default")
      (node (ref "LED29") (pin "A") (pinfunction "A_A") (pintype "passive"))
      (node (ref "SEL3") (pin "3") (pinfunction "1B_3") (pintype "input"))
      (node (ref "SP3") (pin "3") (pinfunction "QA_3") (pintype "output"))
    )
    (net (code "47") (name "/SP9") (class "Default")
      (node (ref "LED30") (pin "A") (pinfunction "A_A") (pintype "passive"))
      (node (ref "SEL3") (pin "6") (pinfunction "2B_6") (pintype "input"))
      (node (ref "SP3") (pin "2") (pinfunction "QB_2") (pintype "output"))
    )
    (net (code "48") (name "/SP10") (class "Default")
      (node (ref "LED31") (pin "A") (pinfunction "A_A") (pintype "passive"))
      (node (ref "SEL3") (pin "10") (pinfunction "3B_10") (pintype "input"))
      (node (ref "SP3") (pin "6") (pinfunction "QC_6") (pintype "output"))
    )
    (net (code "49") (name "/SP11") (class "Default")
      (node (ref "LED32") (pin "A") (pinfunction "A_A") (pintype "passive"))
      (node (ref "SEL3") (pin "13") (pinfunction "4B_13") (pintype "input"))
      (node (ref "SP3") (pin "7") (pinfunction "QD_7") (pintype "output"))
    )
    (net (code "50") (name "/SP_DIR") (class "Default")
      (node (ref "R34") (pin "2") (pinfunction "2_2") (pintype "passive"))
      (node (ref "SP1") (pin "5") (pinfunction "D/~{U}_5") (pintype "input"))
      (node (ref "SP2") (pin "5") (pinfunction "D/~{U}_5") (pintype "input"))
      (node (ref "SP3") (pin "5") (pinfunction "D/~{U}_5") (pintype "input"))
      (node (ref "U$12") (pin "P22") (pinfunction "P22_P22") (pintype "bidirectional"))
    )
    (net (code "51") (name "/WR_RAM2") (class "Default")
      (node (ref "IC1") (pin "8") (pinfunction "O_8") (pintype "output"))
      (node (ref "RAM") (pin "27") (pinfunction "~{WE}_27") (pintype "input"))
    )
    (net (code "52") (name "/~{RD_RAM}") (class "Default")
      (node (ref "R38") (pin "2") (pinfunction "2_2") (pintype "passive"))
      (node (ref "RAM") (pin "22") (pinfunction "~{OE}_22") (pintype "input"))
      (node (ref "U$12") (pin "P23") (pinfunction "P23_P23") (pintype "bidirectional"))
    )
    (net (code "53") (name "/~{WR_MAR}") (class "Default")
      (node (ref "MAR0") (pin "9") (pinfunction "G1_9") (pintype "input"))
      (node (ref "MAR1") (pin "9") (pinfunction "G1_9") (pintype "input"))
      (node (ref "MAR2") (pin "9") (pinfunction "G1_9") (pintype "input"))
      (node (ref "R33") (pin "2") (pinfunction "2_2") (pintype "passive"))
      (node (ref "U$12") (pin "P15") (pinfunction "P15_P15") (pintype "bidirectional"))
    )
    (net (code "54") (name "/~{WR_RAM}") (class "Default")
      (node (ref "IC1") (pin "4") (pinfunction "I0_4") (pintype "input"))
      (node (ref "IC1") (pin "5") (pinfunction "I1_5") (pintype "input"))
      (node (ref "R37") (pin "2") (pinfunction "2_2") (pintype "passive"))
      (node (ref "U$12") (pin "P24") (pinfunction "P24_P24") (pintype "bidirectional"))
    )
    (net (code "55") (name "/~{WR_SP}") (class "Default")
      (node (ref "R35") (pin "2") (pinfunction "2_2") (pintype "passive"))
      (node (ref "SP1") (pin "4") (pinfunction "CTE_4") (pintype "input"))
      (node (ref "U$12") (pin "P17") (pinfunction "P17_P17") (pintype "bidirectional"))
    )
    (net (code "56") (name "GND") (class "Default")
      (node (ref "C8") (pin "-") (pinfunction "-_-") (pintype "passive"))
      (node (ref "MAR0") (pin "1") (pinfunction "M_1") (pintype "input"))
      (node (ref "MAR0") (pin "10") (pinfunction "G2_10") (pintype "input"))
      (node (ref "MAR0") (pin "2") (pinfunction "N_2") (pintype "input"))
      (node (ref "MAR1") (pin "1") (pinfunction "M_1") (pintype "input"))
      (node (ref "MAR1") (pin "10") (pinfunction "G2_10") (pintype "input"))
      (node (ref "MAR1") (pin "2") (pinfunction "N_2") (pintype "input"))
      (node (ref "MAR2") (pin "1") (pinfunction "M_1") (pintype "input"))
      (node (ref "MAR2") (pin "10") (pinfunction "G2_10") (pintype "input"))
      (node (ref "MAR2") (pin "2") (pinfunction "N_2") (pintype "input"))
      (node (ref "R1") (pin "2") (pinfunction "2_2") (pintype "passive"))
      (node (ref "R10") (pin "2") (pinfunction "2_2") (pintype "passive"))
      (node (ref "R11") (pin "2") (pinfunction "2_2") (pintype "passive"))
      (node (ref "R12") (pin "2") (pinfunction "2_2") (pintype "passive"))
      (node (ref "R13") (pin "2") (pinfunction "2_2") (pintype "passive"))
      (node (ref "R14") (pin "2") (pinfunction "2_2") (pintype "passive"))
      (node (ref "R15") (pin "2") (pinfunction "2_2") (pintype "passive"))
      (node (ref "R16") (pin "2") (pinfunction "2_2") (pintype "passive"))
      (node (ref "R17") (pin "2") (pinfunction "2_2") (pintype "passive"))
      (node (ref "R18") (pin "2") (pinfunction "2_2") (pintype "passive"))
      (node (ref "R19") (pin "2") (pinfunction "2_2") (pintype "passive"))
      (node (ref "R2") (pin "2") (pinfunction "2_2") (pintype "passive"))
      (node (ref "R20") (pin "2") (pinfunction "2_2") (pintype "passive"))
      (node (ref "R21") (pin "2") (pinfunction "2_2") (pintype "passive"))
      (node (ref "R22") (pin "2") (pinfunction "2_2") (pintype "passive"))
      (node (ref "R23") (pin "2") (pinfunction "2_2") (pintype "passive"))
      (node (ref "R24") (pin "2") (pinfunction "2_2") (pintype "passive"))
      (node (ref "R25") (pin "2") (pinfunction "2_2") (pintype "passive"))
      (node (ref "R26") (pin "2") (pinfunction "2_2") (pintype "passive"))
      (node (ref "R27") (pin "2") (pinfunction "2_2") (pintype "passive"))
      (node (ref "R28") (pin "2") (pinfunction "2_2") (pintype "passive"))
      (node (ref "R29") (pin "2") (pinfunction "2_2") (pintype "passive"))
      (node (ref "R3") (pin "2") (pinfunction "2_2") (pintype "passive"))
      (node (ref "R30") (pin "2") (pinfunction "2_2") (pintype "passive"))
      (node (ref "R31") (pin "2") (pinfunction "2_2") (pintype "passive"))
      (node (ref "R32") (pin "2") (pinfunction "2_2") (pintype "passive"))
      (node (ref "R4") (pin "2") (pinfunction "2_2") (pintype "passive"))
      (node (ref "R5") (pin "2") (pinfunction "2_2") (pintype "passive"))
      (node (ref "R6") (pin "2") (pinfunction "2_2") (pintype "passive"))
      (node (ref "R7") (pin "2") (pinfunction "2_2") (pintype "passive"))
      (node (ref "R8") (pin "2") (pinfunction "2_2") (pintype "passive"))
      (node (ref "R9") (pin "2") (pinfunction "2_2") (pintype "passive"))
      (node (ref "RAM") (pin "14") (pinfunction "GND_14") (pintype "power_in"))
      (node (ref "RAM") (pin "20") (pinfunction "~{CE}_20") (pintype "input"))
      (node (ref "SEL1") (pin "15") (pinfunction "G_15") (pintype "input"))
      (node (ref "SEL2") (pin "15") (pinfunction "G_15") (pintype "input"))
      (node (ref "SEL3") (pin "15") (pinfunction "G_15") (pintype "input"))
      (node (ref "SP1") (pin "1") (pinfunction "B_1") (pintype "input"))
      (node (ref "SP1") (pin "10") (pinfunction "C_10") (pintype "input"))
      (node (ref "SP1") (pin "15") (pinfunction "A_15") (pintype "input"))
      (node (ref "SP1") (pin "8") (pinfunction "GND_8") (pintype "power_in"))
      (node (ref "SP1") (pin "9") (pinfunction "D_9") (pintype "input"))
      (node (ref "SP2") (pin "1") (pinfunction "B_1") (pintype "input"))
      (node (ref "SP2") (pin "10") (pinfunction "C_10") (pintype "input"))
      (node (ref "SP2") (pin "15") (pinfunction "A_15") (pintype "input"))
      (node (ref "SP2") (pin "8") (pinfunction "GND_8") (pintype "power_in"))
      (node (ref "SP2") (pin "9") (pinfunction "D_9") (pintype "input"))
      (node (ref "SP3") (pin "1") (pinfunction "B_1") (pintype "input"))
      (node (ref "SP3") (pin "10") (pinfunction "C_10") (pintype "input"))
      (node (ref "SP3") (pin "15") (pinfunction "A_15") (pintype "input"))
      (node (ref "SP3") (pin "8") (pinfunction "GND_8") (pintype "power_in"))
      (node (ref "SP3") (pin "9") (pinfunction "D_9") (pintype "input"))
      (node (ref "U$1") (pin "P-") (pinfunction "P-_P-") (pintype "bidirectional"))
      (node (ref "U$10") (pin "P-") (pinfunction "P-_P-") (pintype "bidirectional"))
      (node (ref "U$11") (pin "P-") (pinfunction "P-_P-") (pintype "bidirectional"))
      (node (ref "U$12") (pin "P18") (pinfunction "P18_P18") (pintype "bidirectional"))
      (node (ref "U$12") (pin "P19") (pinfunction "P19_P19") (pintype "bidirectional"))
      (node (ref "U$12") (pin "P20") (pinfunction "P20_P20") (pintype "bidirectional"))
      (node (ref "U$12") (pin "P21") (pinfunction "P21_P21") (pintype "bidirectional"))
      (node (ref "U$2") (pin "P-") (pinfunction "P-_P-") (pintype "bidirectional"))
      (node (ref "U$3") (pin "P-") (pinfunction "P-_P-") (pintype "bidirectional"))
      (node (ref "U$4") (pin "P-") (pinfunction "P-_P-") (pintype "bidirectional"))
      (node (ref "U$5") (pin "P-") (pinfunction "P-_P-") (pintype "bidirectional"))
      (node (ref "U$6") (pin "P-") (pinfunction "P-_P-") (pintype "bidirectional"))
      (node (ref "U$7") (pin "P-") (pinfunction "P-_P-") (pintype "bidirectional"))
      (node (ref "U$8") (pin "P-") (pinfunction "P-_P-") (pintype "bidirectional"))
      (node (ref "U$9") (pin "P-") (pinfunction "P-_P-") (pintype "bidirectional"))
    )
    (net (code "57") (name "Net-(IC1A-O)") (class "Default")
      (node (ref "IC1") (pin "3") (pinfunction "O_3") (pintype "output"))
      (node (ref "IC1") (pin "9") (pinfunction "I0_9") (pintype "input"))
    )
    (net (code "58") (name "Net-(IC1B-O)") (class "Default")
      (node (ref "IC1") (pin "10") (pinfunction "I1_10") (pintype "input"))
      (node (ref "IC1") (pin "6") (pinfunction "O_6") (pintype "output"))
    )
    (net (code "59") (name "Net-(LED1-PadC)") (class "Default")
      (node (ref "LED1") (pin "C") (pinfunction "C_C") (pintype "passive"))
      (node (ref "R1") (pin "1") (pinfunction "1_1") (pintype "passive"))
    )
    (net (code "60") (name "Net-(LED2-PadC)") (class "Default")
      (node (ref "LED2") (pin "C") (pinfunction "C_C") (pintype "passive"))
      (node (ref "R2") (pin "1") (pinfunction "1_1") (pintype "passive"))
    )
    (net (code "61") (name "Net-(LED3-PadC)") (class "Default")
      (node (ref "LED3") (pin "C") (pinfunction "C_C") (pintype "passive"))
      (node (ref "R3") (pin "1") (pinfunction "1_1") (pintype "passive"))
    )
    (net (code "62") (name "Net-(LED4-PadC)") (class "Default")
      (node (ref "LED4") (pin "C") (pinfunction "C_C") (pintype "passive"))
      (node (ref "R4") (pin "1") (pinfunction "1_1") (pintype "passive"))
    )
    (net (code "63") (name "Net-(LED5-PadC)") (class "Default")
      (node (ref "LED5") (pin "C") (pinfunction "C_C") (pintype "passive"))
      (node (ref "R5") (pin "1") (pinfunction "1_1") (pintype "passive"))
    )
    (net (code "64") (name "Net-(LED6-PadC)") (class "Default")
      (node (ref "LED6") (pin "C") (pinfunction "C_C") (pintype "passive"))
      (node (ref "R6") (pin "1") (pinfunction "1_1") (pintype "passive"))
    )
    (net (code "65") (name "Net-(LED7-PadC)") (class "Default")
      (node (ref "LED7") (pin "C") (pinfunction "C_C") (pintype "passive"))
      (node (ref "R7") (pin "1") (pinfunction "1_1") (pintype "passive"))
    )
    (net (code "66") (name "Net-(LED8-PadC)") (class "Default")
      (node (ref "LED8") (pin "C") (pinfunction "C_C") (pintype "passive"))
      (node (ref "R8") (pin "1") (pinfunction "1_1") (pintype "passive"))
    )
    (net (code "67") (name "Net-(LED9-PadC)") (class "Default")
      (node (ref "LED9") (pin "C") (pinfunction "C_C") (pintype "passive"))
      (node (ref "R9") (pin "1") (pinfunction "1_1") (pintype "passive"))
    )
    (net (code "68") (name "Net-(LED10-PadC)") (class "Default")
      (node (ref "LED10") (pin "C") (pinfunction "C_C") (pintype "passive"))
      (node (ref "R10") (pin "1") (pinfunction "1_1") (pintype "passive"))
    )
    (net (code "69") (name "Net-(LED11-PadC)") (class "Default")
      (node (ref "LED11") (pin "C") (pinfunction "C_C") (pintype "passive"))
      (node (ref "R11") (pin "1") (pinfunction "1_1") (pintype "passive"))
    )
    (net (code "70") (name "Net-(LED12-PadC)") (class "Default")
      (node (ref "LED12") (pin "C") (pinfunction "C_C") (pintype "passive"))
      (node (ref "R12") (pin "1") (pinfunction "1_1") (pintype "passive"))
    )
    (net (code "71") (name "Net-(LED13-PadC)") (class "Default")
      (node (ref "LED13") (pin "C") (pinfunction "C_C") (pintype "passive"))
      (node (ref "R13") (pin "1") (pinfunction "1_1") (pintype "passive"))
    )
    (net (code "72") (name "Net-(LED14-PadC)") (class "Default")
      (node (ref "LED14") (pin "C") (pinfunction "C_C") (pintype "passive"))
      (node (ref "R14") (pin "1") (pinfunction "1_1") (pintype "passive"))
    )
    (net (code "73") (name "Net-(LED15-PadC)") (class "Default")
      (node (ref "LED15") (pin "C") (pinfunction "C_C") (pintype "passive"))
      (node (ref "R15") (pin "1") (pinfunction "1_1") (pintype "passive"))
    )
    (net (code "74") (name "Net-(LED16-PadC)") (class "Default")
      (node (ref "LED16") (pin "C") (pinfunction "C_C") (pintype "passive"))
      (node (ref "R16") (pin "1") (pinfunction "1_1") (pintype "passive"))
    )
    (net (code "75") (name "Net-(LED17-PadC)") (class "Default")
      (node (ref "LED17") (pin "C") (pinfunction "C_C") (pintype "passive"))
      (node (ref "R17") (pin "1") (pinfunction "1_1") (pintype "passive"))
    )
    (net (code "76") (name "Net-(LED18-PadC)") (class "Default")
      (node (ref "LED18") (pin "C") (pinfunction "C_C") (pintype "passive"))
      (node (ref "R18") (pin "1") (pinfunction "1_1") (pintype "passive"))
    )
    (net (code "77") (name "Net-(LED19-PadC)") (class "Default")
      (node (ref "LED19") (pin "C") (pinfunction "C_C") (pintype "passive"))
      (node (ref "R19") (pin "1") (pinfunction "1_1") (pintype "passive"))
    )
    (net (code "78") (name "Net-(LED20-PadC)") (class "Default")
      (node (ref "LED20") (pin "C") (pinfunction "C_C") (pintype "passive"))
      (node (ref "R20") (pin "1") (pinfunction "1_1") (pintype "passive"))
    )
    (net (code "79") (name "Net-(LED21-PadC)") (class "Default")
      (node (ref "LED21") (pin "C") (pinfunction "C_C") (pintype "passive"))
      (node (ref "R21") (pin "1") (pinfunction "1_1") (pintype "passive"))
    )
    (net (code "80") (name "Net-(LED22-PadC)") (class "Default")
      (node (ref "LED22") (pin "C") (pinfunction "C_C") (pintype "passive"))
      (node (ref "R22") (pin "1") (pinfunction "1_1") (pintype "passive"))
    )
    (net (code "81") (name "Net-(LED23-PadC)") (class "Default")
      (node (ref "LED23") (pin "C") (pinfunction "C_C") (pintype "passive"))
      (node (ref "R23") (pin "1") (pinfunction "1_1") (pintype "passive"))
    )
    (net (code "82") (name "Net-(LED24-PadC)") (class "Default")
      (node (ref "LED24") (pin "C") (pinfunction "C_C") (pintype "passive"))
      (node (ref "R24") (pin "1") (pinfunction "1_1") (pintype "passive"))
    )
    (net (code "83") (name "Net-(LED25-PadC)") (class "Default")
      (node (ref "LED25") (pin "C") (pinfunction "C_C") (pintype "passive"))
      (node (ref "R25") (pin "1") (pinfunction "1_1") (pintype "passive"))
    )
    (net (code "84") (name "Net-(LED26-PadC)") (class "Default")
      (node (ref "LED26") (pin "C") (pinfunction "C_C") (pintype "passive"))
      (node (ref "R26") (pin "1") (pinfunction "1_1") (pintype "passive"))
    )
    (net (code "85") (name "Net-(LED27-PadC)") (class "Default")
      (node (ref "LED27") (pin "C") (pinfunction "C_C") (pintype "passive"))
      (node (ref "R27") (pin "1") (pinfunction "1_1") (pintype "passive"))
    )
    (net (code "86") (name "Net-(LED28-PadC)") (class "Default")
      (node (ref "LED28") (pin "C") (pinfunction "C_C") (pintype "passive"))
      (node (ref "R28") (pin "1") (pinfunction "1_1") (pintype "passive"))
    )
    (net (code "87") (name "Net-(LED29-PadC)") (class "Default")
      (node (ref "LED29") (pin "C") (pinfunction "C_C") (pintype "passive"))
      (node (ref "R29") (pin "1") (pinfunction "1_1") (pintype "passive"))
    )
    (net (code "88") (name "Net-(LED30-PadC)") (class "Default")
      (node (ref "LED30") (pin "C") (pinfunction "C_C") (pintype "passive"))
      (node (ref "R30") (pin "1") (pinfunction "1_1") (pintype "passive"))
    )
    (net (code "89") (name "Net-(LED31-PadC)") (class "Default")
      (node (ref "LED31") (pin "C") (pinfunction "C_C") (pintype "passive"))
      (node (ref "R31") (pin "1") (pinfunction "1_1") (pintype "passive"))
    )
    (net (code "90") (name "Net-(LED32-PadC)") (class "Default")
      (node (ref "LED32") (pin "C") (pinfunction "C_C") (pintype "passive"))
      (node (ref "R32") (pin "1") (pinfunction "1_1") (pintype "passive"))
    )
    (net (code "91") (name "Net-(R33-Pad1)") (class "Default")
      (node (ref "R33") (pin "1") (pinfunction "1_1") (pintype "passive"))
      (node (ref "WR_MAR") (pin "C") (pinfunction "C_C") (pintype "passive"))
    )
    (net (code "92") (name "Net-(R34-Pad1)") (class "Default")
      (node (ref "R34") (pin "1") (pinfunction "1_1") (pintype "passive"))
      (node (ref "SP_DIR") (pin "C") (pinfunction "C_C") (pintype "passive"))
    )
    (net (code "93") (name "Net-(R35-Pad1)") (class "Default")
      (node (ref "R35") (pin "1") (pinfunction "1_1") (pintype "passive"))
      (node (ref "WR_SP") (pin "C") (pinfunction "C_C") (pintype "passive"))
    )
    (net (code "94") (name "Net-(R36-Pad1)") (class "Default")
      (node (ref "R36") (pin "1") (pinfunction "1_1") (pintype "passive"))
      (node (ref "SEL_MAR/SP") (pin "C") (pinfunction "C_C") (pintype "passive"))
    )
    (net (code "95") (name "Net-(R37-Pad1)") (class "Default")
      (node (ref "R37") (pin "1") (pinfunction "1_1") (pintype "passive"))
      (node (ref "WR_RAM") (pin "C") (pinfunction "C_C") (pintype "passive"))
    )
    (net (code "96") (name "Net-(R38-Pad1)") (class "Default")
      (node (ref "R38") (pin "1") (pinfunction "1_1") (pintype "passive"))
      (node (ref "RD_RAM") (pin "C") (pinfunction "C_C") (pintype "passive"))
    )
    (net (code "97") (name "VCC") (class "Default")
      (node (ref "C8") (pin "+") (pinfunction "+_+") (pintype "passive"))
      (node (ref "IC1") (pin "12") (pinfunction "I0_12") (pintype "input"))
      (node (ref "IC1") (pin "13") (pinfunction "I1_13") (pintype "input"))
      (node (ref "RAM") (pin "28") (pinfunction "VCC_28") (pintype "power_in"))
      (node (ref "RD_RAM") (pin "A") (pinfunction "A_A") (pintype "passive"))
      (node (ref "SEL_MAR/SP") (pin "A") (pinfunction "A_A") (pintype "passive"))
      (node (ref "SP1") (pin "11") (pinfunction "LD_11") (pintype "input"))
      (node (ref "SP1") (pin "16") (pinfunction "VCC_16") (pintype "power_in"))
      (node (ref "SP2") (pin "11") (pinfunction "LD_11") (pintype "input"))
      (node (ref "SP2") (pin "16") (pinfunction "VCC_16") (pintype "power_in"))
      (node (ref "SP3") (pin "11") (pinfunction "LD_11") (pintype "input"))
      (node (ref "SP3") (pin "16") (pinfunction "VCC_16") (pintype "power_in"))
      (node (ref "SP_DIR") (pin "A") (pinfunction "A_A") (pintype "passive"))
      (node (ref "U$1") (pin "P+") (pinfunction "P+_P+") (pintype "bidirectional"))
      (node (ref "U$10") (pin "P+") (pinfunction "P+_P+") (pintype "bidirectional"))
      (node (ref "U$11") (pin "P+") (pinfunction "P+_P+") (pintype "bidirectional"))
      (node (ref "U$12") (pin "P0") (pinfunction "P0_P0") (pintype "bidirectional"))
      (node (ref "U$12") (pin "P1") (pinfunction "P1_P1") (pintype "bidirectional"))
      (node (ref "U$12") (pin "P38") (pinfunction "P38_P38") (pintype "bidirectional"))
      (node (ref "U$12") (pin "P39") (pinfunction "P39_P39") (pintype "bidirectional"))
      (node (ref "U$2") (pin "P+") (pinfunction "P+_P+") (pintype "bidirectional"))
      (node (ref "U$3") (pin "P+") (pinfunction "P+_P+") (pintype "bidirectional"))
      (node (ref "U$4") (pin "P+") (pinfunction "P+_P+") (pintype "bidirectional"))
      (node (ref "U$5") (pin "P+") (pinfunction "P+_P+") (pintype "bidirectional"))
      (node (ref "U$6") (pin "P+") (pinfunction "P+_P+") (pintype "bidirectional"))
      (node (ref "U$7") (pin "P+") (pinfunction "P+_P+") (pintype "bidirectional"))
      (node (ref "U$8") (pin "P+") (pinfunction "P+_P+") (pintype "bidirectional"))
      (node (ref "U$9") (pin "P+") (pinfunction "P+_P+") (pintype "bidirectional"))
      (node (ref "WR_MAR") (pin "A") (pinfunction "A_A") (pintype "passive"))
      (node (ref "WR_RAM") (pin "A") (pinfunction "A_A") (pintype "passive"))
      (node (ref "WR_SP") (pin "A") (pinfunction "A_A") (pintype "passive"))
    )
    (net (code "98") (name "unconnected-(IC1D-O-Pad11)") (class "Default")
      (node (ref "IC1") (pin "11") (pinfunction "O_11") (pintype "output"))
    )
    (net (code "99") (name "unconnected-(RAM-NC-Pad1)") (class "Default")
      (node (ref "RAM") (pin "1") (pinfunction "NC_1") (pintype "no_connect"))
    )
    (net (code "100") (name "unconnected-(RAM-NC-Pad26)") (class "Default")
      (node (ref "RAM") (pin "26") (pinfunction "NC_26") (pintype "no_connect"))
    )
    (net (code "101") (name "unconnected-(SP1A-MX{slash}MN-Pad12)") (class "Default")
      (node (ref "SP1") (pin "12") (pinfunction "MX/MN_12") (pintype "output"))
    )
    (net (code "102") (name "unconnected-(SP2A-MX{slash}MN-Pad12)") (class "Default")
      (node (ref "SP2") (pin "12") (pinfunction "MX/MN_12") (pintype "output"))
    )
    (net (code "103") (name "unconnected-(SP3A-MX{slash}MN-Pad12)") (class "Default")
      (node (ref "SP3") (pin "12") (pinfunction "MX/MN_12") (pintype "output"))
    )
    (net (code "104") (name "unconnected-(SP3A-RCO-Pad13)") (class "Default")
      (node (ref "SP3") (pin "13") (pinfunction "RCO_13") (pintype "output"))
    )
    (net (code "105") (name "unconnected-(U$12-PadP8)") (class "Default")
      (node (ref "U$12") (pin "P8") (pinfunction "P8_P8") (pintype "bidirectional"))
    )
    (net (code "106") (name "unconnected-(U$12-PadP9)") (class "Default")
      (node (ref "U$12") (pin "P9") (pinfunction "P9_P9") (pintype "bidirectional"))
    )
    (net (code "107") (name "unconnected-(U$12-PadP10)") (class "Default")
      (node (ref "U$12") (pin "P10") (pinfunction "P10_P10") (pintype "bidirectional"))
    )
    (net (code "108") (name "unconnected-(U$12-PadP11)") (class "Default")
      (node (ref "U$12") (pin "P11") (pinfunction "P11_P11") (pintype "bidirectional"))
    )
    (net (code "109") (name "unconnected-(U$12-PadP12)") (class "Default")
      (node (ref "U$12") (pin "P12") (pinfunction "P12_P12") (pintype "bidirectional"))
    )
    (net (code "110") (name "unconnected-(U$12-PadP13)") (class "Default")
      (node (ref "U$12") (pin "P13") (pinfunction "P13_P13") (pintype "bidirectional"))
    )
    (net (code "111") (name "unconnected-(U$12-PadP14)") (class "Default")
      (node (ref "U$12") (pin "P14") (pinfunction "P14_P14") (pintype "bidirectional"))
    )
    (net (code "112") (name "unconnected-(U$12-PadP25)") (class "Default")
      (node (ref "U$12") (pin "P25") (pinfunction "P25_P25") (pintype "bidirectional"))
    )
    (net (code "113") (name "unconnected-(U$12-PadP26)") (class "Default")
      (node (ref "U$12") (pin "P26") (pinfunction "P26_P26") (pintype "bidirectional"))
    )
    (net (code "114") (name "unconnected-(U$12-PadP27)") (class "Default")
      (node (ref "U$12") (pin "P27") (pinfunction "P27_P27") (pintype "bidirectional"))
    )
    (net (code "115") (name "unconnected-(U$12-PadP28)") (class "Default")
      (node (ref "U$12") (pin "P28") (pinfunction "P28_P28") (pintype "bidirectional"))
    )
    (net (code "116") (name "unconnected-(U$12-PadP29)") (class "Default")
      (node (ref "U$12") (pin "P29") (pinfunction "P29_P29") (pintype "bidirectional"))
    )
    (net (code "117") (name "unconnected-(U$12-PadP30)") (class "Default")
      (node (ref "U$12") (pin "P30") (pinfunction "P30_P30") (pintype "bidirectional"))
    )
    (net (code "118") (name "unconnected-(U$12-PadP31)") (class "Default")
      (node (ref "U$12") (pin "P31") (pinfunction "P31_P31") (pintype "bidirectional"))
    )
    (net (code "119") (name "unconnected-(U$12-PadP32)") (class "Default")
      (node (ref "U$12") (pin "P32") (pinfunction "P32_P32") (pintype "bidirectional"))
    )
    (net (code "120") (name "unconnected-(U$12-PadP33)") (class "Default")
      (node (ref "U$12") (pin "P33") (pinfunction "P33_P33") (pintype "bidirectional"))
    )
  )
)
